# v3_1.net
KiCad netlist of a schematic drawn in EasyEDA Pro
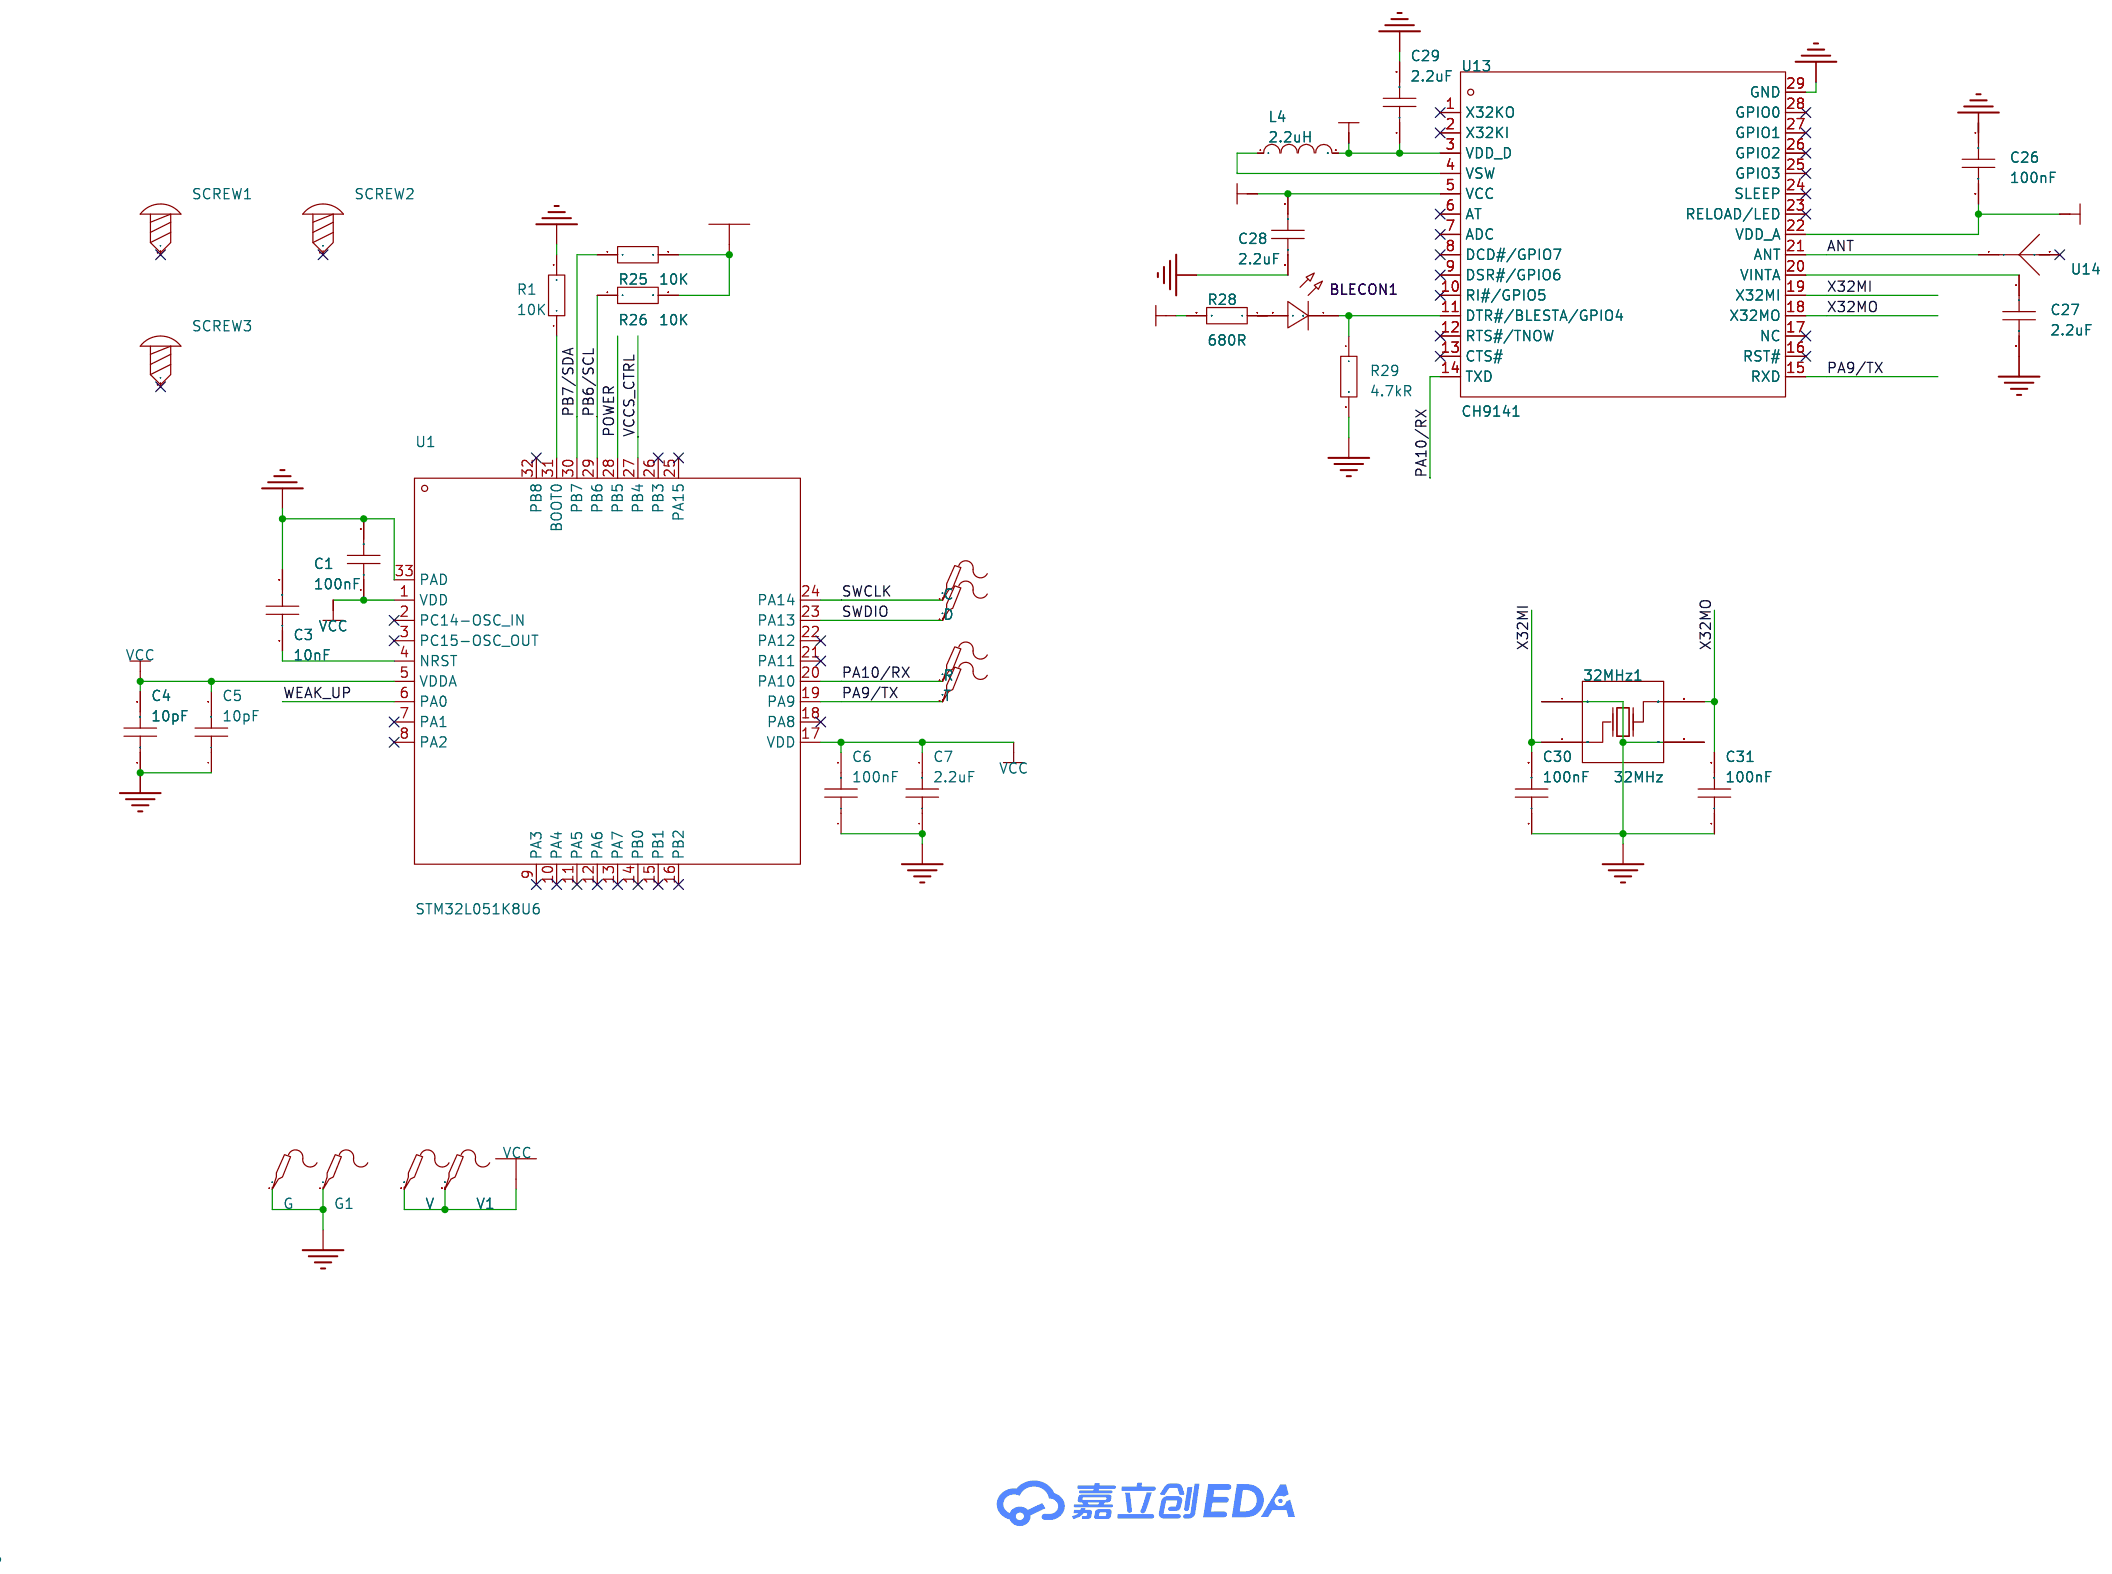
[diagram p0: 主控]
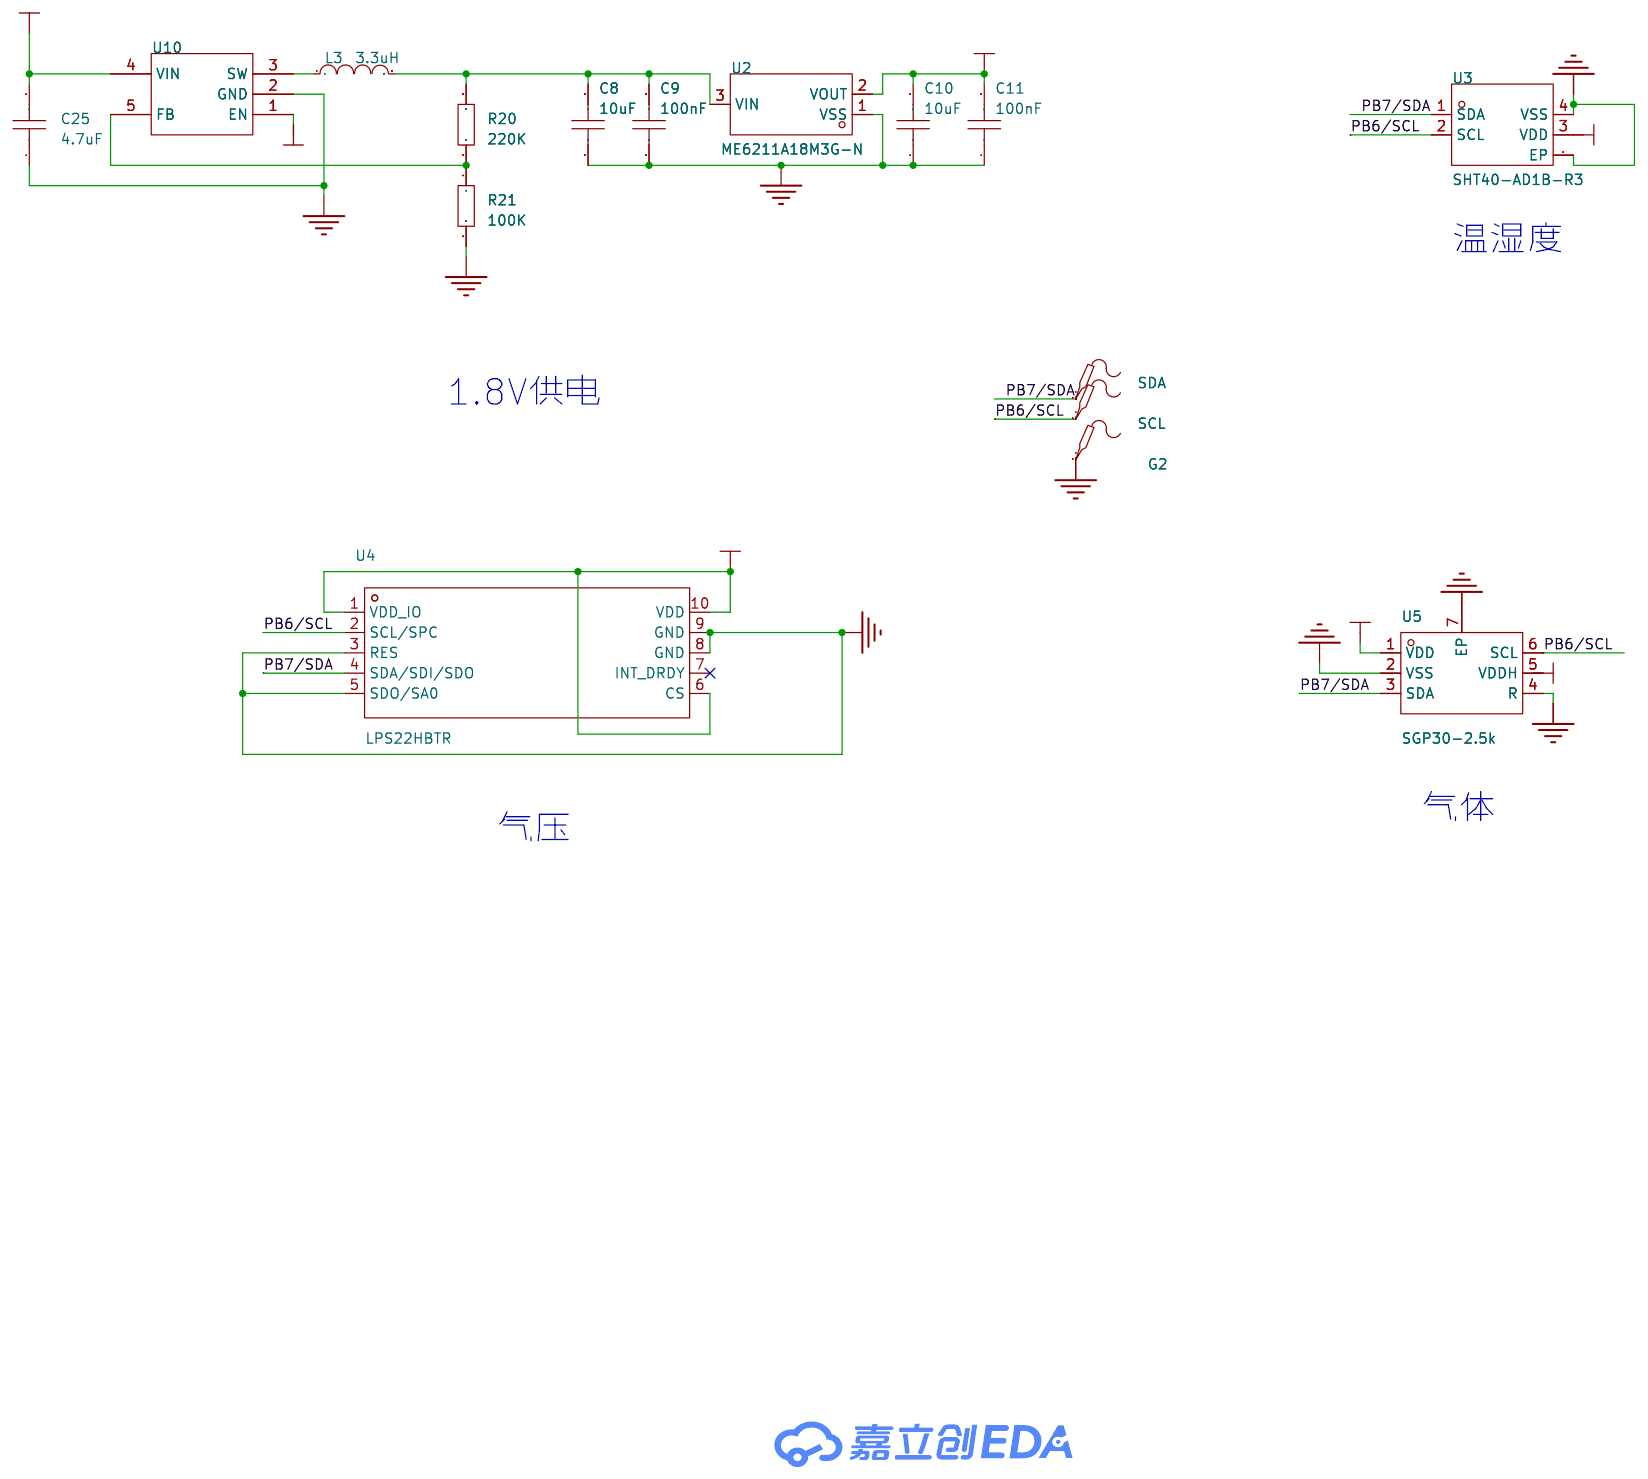
[diagram p1: 传感器]
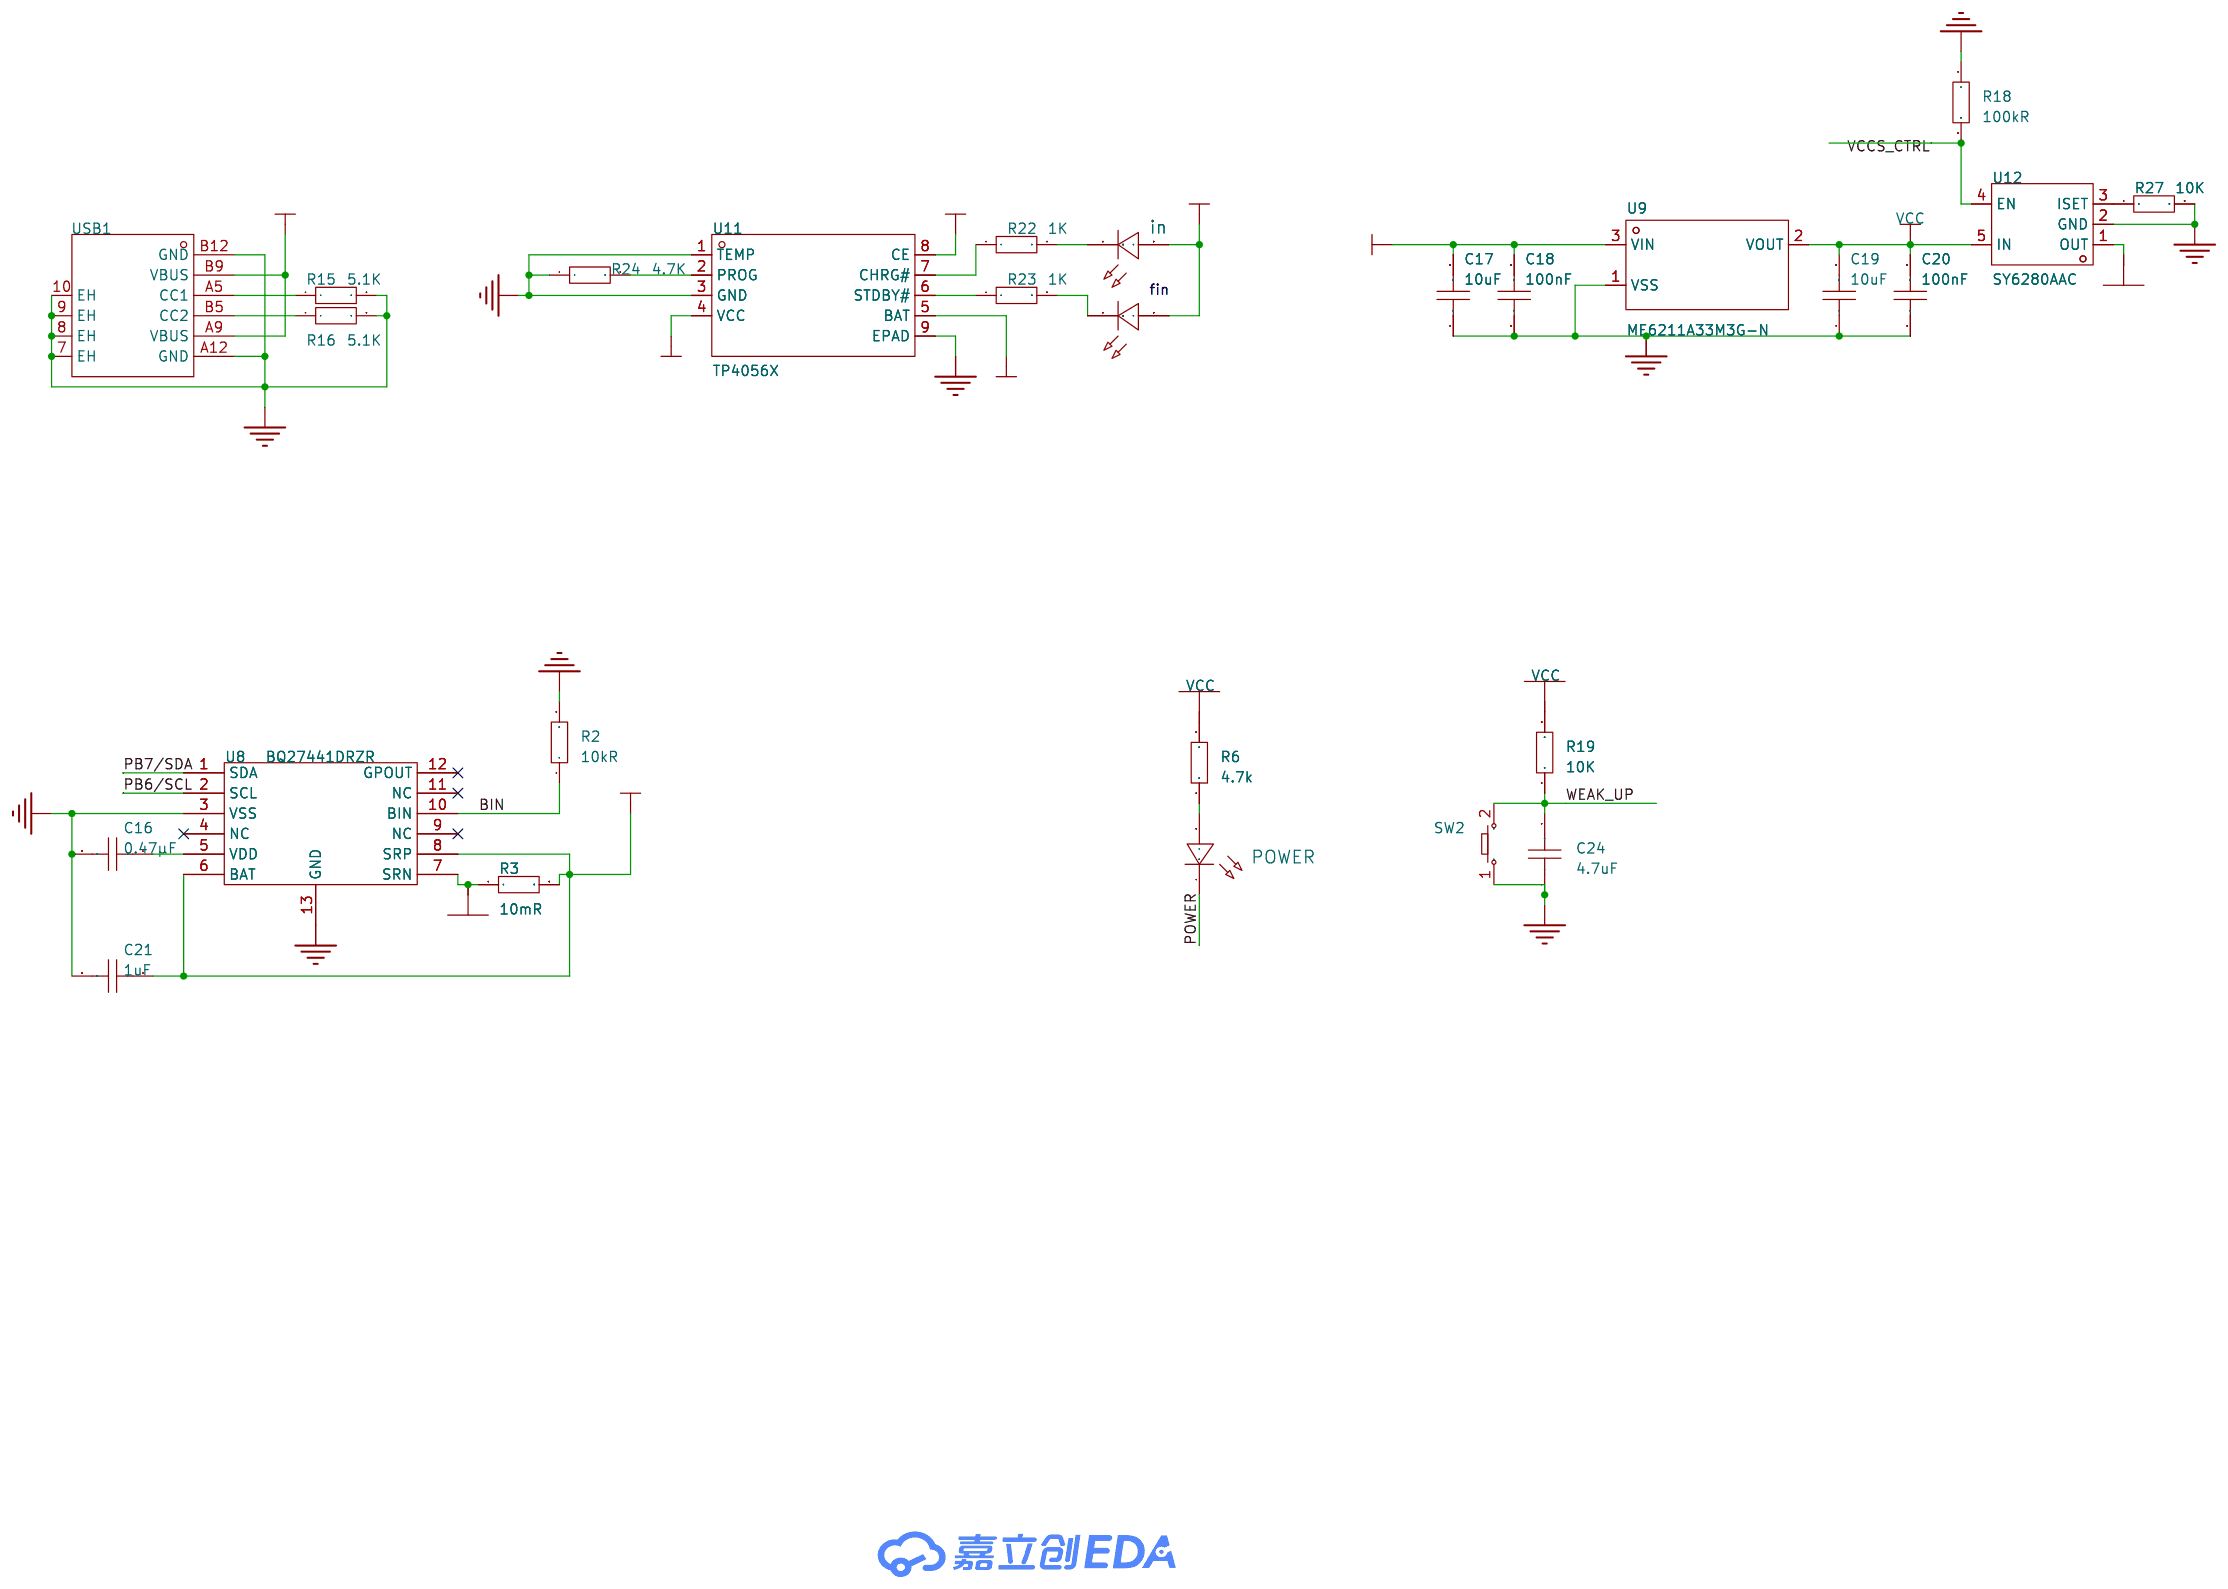
[diagram p2: 电源]

(export (version "E")
  (design (tool "Eeschema 10.0.6"))
  (components
    (comp (ref "32MHz1")
      (value "32MHz")
      (footprint "easyedapro:OSC-SMD_4P-L3.2-W2.5-BL")
      (description "晶振类型:贴片晶振;频率:32MHz;常温频差:±10ppm;外接负载电容:10pF;频率稳定度(全温):±20ppm;")
      (fields (field (name "Manufacturer Part") "X322532MMB4SI") (field (name "Manufacturer") "YXC(扬兴晶振)"))
      (libsource (lib "easyedapro") (part "X322532MMB4SI"))
    )
    (comp (ref "BLECON1")
      (value "~")
      (footprint "easyedapro:LED_0603")
      (libsource (lib "easyedapro") (part "LED_B"))
    )
    (comp (ref "C")
      (value "~")
      (footprint "easyedapro:Test-Point-0.5mm")
      (description "Test Point 测试点")
      (libsource (lib "easyedapro") (part "Test-Point"))
    )
    (comp (ref "C1")
      (value "100nF")
      (footprint "easyedapro:C0603")
      (libsource (lib "easyedapro") (part "CapAcitance"))
    )
    (comp (ref "C3")
      (value "10nF")
      (footprint "easyedapro:C0603")
      (libsource (lib "easyedapro") (part "CapAcitance"))
    )
    (comp (ref "C4")
      (value "10pF")
      (footprint "easyedapro:C0603")
      (libsource (lib "easyedapro") (part "CapAcitance"))
    )
    (comp (ref "C5")
      (value "10pF")
      (footprint "easyedapro:C0603")
      (libsource (lib "easyedapro") (part "CapAcitance"))
    )
    (comp (ref "C6")
      (value "100nF")
      (footprint "easyedapro:C0603")
      (libsource (lib "easyedapro") (part "CapAcitance"))
    )
    (comp (ref "C7")
      (value "2.2uF")
      (footprint "easyedapro:C0603")
      (libsource (lib "easyedapro") (part "CapAcitance"))
    )
    (comp (ref "C26")
      (value "100nF")
      (footprint "easyedapro:C0603")
      (libsource (lib "easyedapro") (part "CapAcitance"))
    )
    (comp (ref "C27")
      (value "2.2uF")
      (footprint "easyedapro:C0603")
      (libsource (lib "easyedapro") (part "CapAcitance"))
    )
    (comp (ref "C28")
      (value "2.2uF")
      (footprint "easyedapro:C0603")
      (libsource (lib "easyedapro") (part "CapAcitance"))
    )
    (comp (ref "C29")
      (value "2.2uF")
      (footprint "easyedapro:C0603")
      (libsource (lib "easyedapro") (part "CapAcitance"))
    )
    (comp (ref "C30")
      (value "100nF")
      (footprint "easyedapro:C0603")
      (libsource (lib "easyedapro") (part "CapAcitance"))
    )
    (comp (ref "C31")
      (value "100nF")
      (footprint "easyedapro:C0603")
      (libsource (lib "easyedapro") (part "CapAcitance"))
    )
    (comp (ref "D")
      (value "~")
      (footprint "easyedapro:Test-Point-0.5mm")
      (description "Test Point 测试点")
      (libsource (lib "easyedapro") (part "Test-Point"))
    )
    (comp (ref "G")
      (value "~")
      (footprint "easyedapro:Test-Point-0.5mm")
      (description "Test Point 测试点")
      (libsource (lib "easyedapro") (part "Test-Point"))
    )
    (comp (ref "G1")
      (value "~")
      (footprint "easyedapro:Test-Point-0.5mm")
      (description "Test Point 测试点")
      (libsource (lib "easyedapro") (part "Test-Point"))
    )
    (comp (ref "L4")
      (value "2.2uH")
      (footprint "easyedapro:L0603")
      (libsource (lib "easyedapro") (part "SDFL1608S100KTF"))
    )
    (comp (ref "R")
      (value "~")
      (footprint "easyedapro:Test-Point-0.5mm")
      (description "Test Point 测试点")
      (libsource (lib "easyedapro") (part "Test-Point"))
    )
    (comp (ref "R1") (value "10K") (footprint "easyedapro:R0603") (libsource (lib "easyedapro") (part "电阻")))
    (comp (ref "R25") (value "10K") (footprint "easyedapro:R0603") (libsource (lib "easyedapro") (part "电阻")))
    (comp (ref "R26") (value "10K") (footprint "easyedapro:R0603") (libsource (lib "easyedapro") (part "电阻")))
    (comp (ref "R28")
      (value "680R")
      (footprint "easyedapro:R0603")
      (libsource (lib "easyedapro") (part "电阻"))
    )
    (comp (ref "R29")
      (value "4.7kR")
      (footprint "easyedapro:R0603")
      (libsource (lib "easyedapro") (part "电阻"))
    )
    (comp (ref "SCREW1")
      (value "~")
      (footprint "easyedapro:M2螺丝")
      (libsource (lib "easyedapro") (part "螺丝孔"))
    )
    (comp (ref "SCREW2")
      (value "~")
      (footprint "easyedapro:M2螺丝")
      (libsource (lib "easyedapro") (part "螺丝孔"))
    )
    (comp (ref "SCREW3")
      (value "~")
      (footprint "easyedapro:M2螺丝")
      (libsource (lib "easyedapro") (part "螺丝孔"))
    )
    (comp (ref "T")
      (value "~")
      (footprint "easyedapro:Test-Point-0.5mm")
      (description "Test Point 测试点")
      (libsource (lib "easyedapro") (part "Test-Point"))
    )
    (comp (ref "U1")
      (value "STM32L051K8U6")
      (footprint "easyedapro:UFQFPN-32_L5.0-W5.0-P0.50-BL-EP")
      (description "CPU内核:ARM-M系列;CPU最大主频:32MHz;应用领域:-;")
      (fields (field (name "Manufacturer") "ST(意法半导体)"))
      (libsource (lib "easyedapro") (part "STM32L051K8U6"))
    )
    (comp (ref "U13")
      (value "CH9141")
      (footprint "easyedapro:qfn-28_l4.0-w4.0-p0.40-bl-ep2.7")
      (fields (field (name "Manufacturer") "WCH(南京沁恒)"))
      (libsource (lib "easyedapro") (part "CH9141"))
    )
    (comp (ref "U14")
      (value "~")
      (footprint "easyedapro:SMD，3.5x1.8")
      (libsource (lib "easyedapro") (part "T3518"))
    )
    (comp (ref "V")
      (value "~")
      (footprint "easyedapro:Test-Point-0.5mm")
      (description "Test-Point")
      (libsource (lib "") (part "Test-Point_1"))
    )
    (comp (ref "V1")
      (value "~")
      (footprint "easyedapro:Test-Point-0.5mm")
      (description "Test-Point")
      (libsource (lib "") (part "Test-Point_1"))
    )
    (comp (ref "C8")
      (value "10uF")
      (footprint "easyedapro:C0603")
      (libsource (lib "easyedapro") (part "CapAcitance"))
    )
    (comp (ref "C9")
      (value "100nF")
      (footprint "easyedapro:C0603")
      (libsource (lib "easyedapro") (part "CapAcitance"))
    )
    (comp (ref "C10")
      (value "10uF")
      (footprint "easyedapro:C0603")
      (libsource (lib "easyedapro") (part "CapAcitance"))
    )
    (comp (ref "C11")
      (value "100nF")
      (footprint "easyedapro:C0603")
      (libsource (lib "easyedapro") (part "CapAcitance"))
    )
    (comp (ref "C25")
      (value "4.7uF")
      (footprint "easyedapro:C0603")
      (libsource (lib "easyedapro") (part "CapAcitance"))
    )
    (comp (ref "G2")
      (value "~")
      (footprint "easyedapro:Test-Point-0.5mm")
      (description "Test-Point")
      (libsource (lib "easyedapro") (part "Test-Point"))
    )
    (comp (ref "L3")
      (value "3.3uH")
      (footprint "easyedapro:IND-SMD_L2.5-W2.0_SWPA2520")
      (description "电感值:2.2uH;精度:±20%;额定电流:1.25A;直流电阻(DCR):216mΩ;")
      (fields
        (field (name "Manufacturer Part") "SWPA252012S2R2MT")
        (field (name "Manufacturer") "Sunlord(顺络)")
      )
      (libsource (lib "easyedapro") (part "SWPA252012S-2R2MT"))
    )
    (comp (ref "R20")
      (value "220K")
      (footprint "easyedapro:R0603")
      (libsource (lib "easyedapro") (part "电阻"))
    )
    (comp (ref "R21")
      (value "100K")
      (footprint "easyedapro:R0603")
      (libsource (lib "easyedapro") (part "电阻"))
    )
    (comp (ref "SCL")
      (value "~")
      (footprint "easyedapro:Test-Point-0.5mm")
      (description "Test-Point")
      (libsource (lib "easyedapro") (part "Test-Point"))
    )
    (comp (ref "SDA")
      (value "~")
      (footprint "easyedapro:Test-Point-0.5mm")
      (description "Test-Point")
      (libsource (lib "easyedapro") (part "Test-Point"))
    )
    (comp (ref "U2")
      (value "ME6211A18M3G-N")
      (footprint "easyedapro:SOT-23-3_L3.0-W1.7-P0.95-LS2.9-BR")
      (description "输出类型:固定;最大输入电压:6V;输出电压:1.8V;最大输出电流:300mA;电源纹波抑制比(PSRR):70dB;输出极性:正极;")
      (fields (field (name "Manufacturer") "MICRONE(南京微盟)"))
      (libsource (lib "easyedapro") (part "ME6211A18M3G-N"))
    )
    (comp (ref "U3")
      (value "SHT40-AD1B-R3")
      (footprint "easyedapro:DFN-4_L1.5-W1.5-P0.8-TL-EP")
      (description "3.000.353")
      (fields (field (name "Manufacturer") "Sensirion(瑞士盛思锐)"))
      (libsource (lib "easyedapro") (part "SHT40-AD1B-R3"))
    )
    (comp (ref "U4")
      (value "LPS22HBTR")
      (footprint "easyedapro:HLGA-10L_LPS22HBTR")
      (fields (field (name "Manufacturer") "ST(意法半导体)"))
      (libsource (lib "easyedapro") (part "LPS22HBTR"))
    )
    (comp (ref "U5")
      (value "SGP30-2.5k")
      (footprint "easyedapro:DFN-6_L2.5-W2.5-P0.8-BL-EP")
      (description "气体类型:空气质量;精度:±10%;")
      (fields (field (name "Manufacturer") "Sensirion(瑞士盛思锐)"))
      (libsource (lib "easyedapro") (part "SGP30-2.5K"))
    )
    (comp (ref "U10")
      (value "~")
      (footprint "easyedapro:SOT-23-5_L2.9-W1.6-P0.95-LS2.8-TL")
      (libsource (lib "easyedapro") (part "TLV62569DBVR"))
    )
    (comp (ref "C16")
      (value "0.47μF")
      (footprint "easyedapro:C0603")
      (libsource (lib "easyedapro") (part "CapAcitance"))
    )
    (comp (ref "C17")
      (value "10uF")
      (footprint "easyedapro:C0603")
      (libsource (lib "easyedapro") (part "CapAcitance"))
    )
    (comp (ref "C18")
      (value "100nF")
      (footprint "easyedapro:C0603")
      (libsource (lib "easyedapro") (part "CapAcitance"))
    )
    (comp (ref "C19")
      (value "10uF")
      (footprint "easyedapro:C0603")
      (libsource (lib "easyedapro") (part "CapAcitance"))
    )
    (comp (ref "C20")
      (value "100nF")
      (footprint "easyedapro:C0603")
      (libsource (lib "easyedapro") (part "CapAcitance"))
    )
    (comp (ref "C21")
      (value "1uF")
      (footprint "easyedapro:C0603")
      (libsource (lib "easyedapro") (part "CapAcitance"))
    )
    (comp (ref "C24")
      (value "4.7uF")
      (footprint "easyedapro:C0603")
      (libsource (lib "easyedapro") (part "CapAcitance"))
    )
    (comp (ref "fin")
      (value "~")
      (footprint "easyedapro:LED_0603")
      (libsource (lib "easyedapro") (part "LED_G"))
    )
    (comp (ref "in")
      (value "~")
      (footprint "easyedapro:LED_0603")
      (libsource (lib "easyedapro") (part "LED_R"))
    )
    (comp (ref "POWER")
      (value "~")
      (footprint "easyedapro:LED_0603")
      (libsource (lib "easyedapro") (part "LED_R"))
    )
    (comp (ref "R2") (value "10kR") (libsource (lib "easyedapro") (part "电阻")))
    (comp (ref "R3") (value "10mR") (libsource (lib "easyedapro") (part "电阻")))
    (comp (ref "R6") (value "4.7k") (footprint "easyedapro:R0603") (libsource (lib "easyedapro") (part "电阻")))
    (comp (ref "R15")
      (value "5.1K")
      (footprint "easyedapro:R0603")
      (libsource (lib "easyedapro") (part "电阻"))
    )
    (comp (ref "R16")
      (value "5.1K")
      (footprint "easyedapro:R0603")
      (libsource (lib "easyedapro") (part "电阻"))
    )
    (comp (ref "R18") (value "100kR") (libsource (lib "easyedapro") (part "电阻")))
    (comp (ref "R19") (value "10K") (footprint "easyedapro:R0603") (libsource (lib "easyedapro") (part "电阻")))
    (comp (ref "R22") (value "1K") (footprint "easyedapro:R0603") (libsource (lib "easyedapro") (part "电阻")))
    (comp (ref "R23") (value "1K") (footprint "easyedapro:R0603") (libsource (lib "easyedapro") (part "电阻")))
    (comp (ref "R24")
      (value "4.7K")
      (footprint "easyedapro:R0603")
      (libsource (lib "easyedapro") (part "电阻"))
    )
    (comp (ref "R27") (value "10K") (footprint "easyedapro:R0603") (libsource (lib "easyedapro") (part "电阻")))
    (comp (ref "SW2")
      (value "~")
      (footprint "easyedapro:Key_SMD_3.6x6.1x2.5")
      (libsource (lib "easyedapro") (part "轻触按键x2"))
    )
    (comp (ref "U8")
      (value "BQ27441DRZR")
      (footprint "easyedapro:VSON-12")
      (libsource (lib "easyedapro") (part "BQ27441DRZR"))
    )
    (comp (ref "U9")
      (value "ME6211A33M3G-N")
      (footprint "easyedapro:SOT-23-3_L2.9-W1.6-P1.90-LS2.8-BR")
      (description "输出类型:固定;最大输入电压:6V;输出电压:3.3V;最大输出电流:500mA;电源纹波抑制比(PSRR):70dB;输出极性:正极;")
      (fields (field (name "Manufacturer") "MICRONE(南京微盟)"))
      (libsource (lib "easyedapro") (part "ME6211A33M3G-N"))
    )
    (comp (ref "U11")
      (value "TP4056X")
      (footprint "easyedapro:SOP-8_L4.9-W3.9-P1.27-LS6.0-BL-EP")
      (description "充电电池的类型:-;电池单元组数:-;最大充电电流:-;充满的电池组电压:-;最大供应电压:-;")
      (fields (field (name "Manufacturer") "TOPPOWER(南京拓微)"))
      (libsource (lib "easyedapro") (part "TP4056X"))
    )
    (comp (ref "U12")
      (value "SY6280AAC")
      (footprint "easyedapro:SOT-23-5_L3.0-W1.7-P0.95-LS2.8-BR")
      (description "低能耗配电开关")
      (fields (field (name "Manufacturer") "矽力杰silergy"))
      (libsource (lib "easyedapro") (part "SY6280AAC"))
    )
    (comp (ref "USB1")
      (value "~")
      (footprint "easyedapro:USB_ TYPE-C-6P")
      (libsource (lib "easyedapro") (part "USB_ TYPE-C-6P"))
    )
  )
  (nets
    (net (code "1") (name "1.8V") (class "Default")
      (node (ref "C10") (pin "2") (pinfunction "2_2") (pintype "input"))
      (node (ref "C11") (pin "2") (pinfunction "2_2") (pintype "input"))
      (node (ref "U2") (pin "2") (pinfunction "VOUT_2") (pintype "unspecified"))
      (node (ref "U5") (pin "1") (pinfunction "VDD_1") (pintype "unspecified"))
      (node (ref "U5") (pin "5") (pinfunction "VDDH_5") (pintype "unspecified"))
    )
    (net (code "2") (name "ANT") (class "Default")
      (node (ref "U13") (pin "21") (pinfunction "ANT_21") (pintype "unspecified"))
      (node (ref "U14") (pin "1") (pinfunction "1_1") (pintype "unspecified"))
    )
    (net (code "3") (name "BAT") (class "Default")
      (node (ref "R3") (pin "1") (pinfunction "1_1") (pintype "input"))
      (node (ref "U8") (pin "7") (pinfunction "SRN_7") (pintype "input"))
    )
    (net (code "4") (name "BIN") (class "Default")
      (node (ref "R2") (pin "1") (pinfunction "1_1") (pintype "input"))
      (node (ref "U8") (pin "10") (pinfunction "BIN_10") (pintype "input"))
    )
    (net (code "5") (name "GND") (class "Default")
      (node (ref "32MHz1") (pin "2") (pinfunction "GND_2") (pintype "input"))
      (node (ref "32MHz1") (pin "4") (pinfunction "GND_4") (pintype "input"))
      (node (ref "C1") (pin "2") (pinfunction "2_2") (pintype "input"))
      (node (ref "C10") (pin "1") (pinfunction "1_1") (pintype "input"))
      (node (ref "C11") (pin "1") (pinfunction "1_1") (pintype "input"))
      (node (ref "C16") (pin "2") (pinfunction "2_2") (pintype "input"))
      (node (ref "C17") (pin "1") (pinfunction "1_1") (pintype "input"))
      (node (ref "C18") (pin "1") (pinfunction "1_1") (pintype "input"))
      (node (ref "C19") (pin "1") (pinfunction "1_1") (pintype "input"))
      (node (ref "C20") (pin "1") (pinfunction "1_1") (pintype "input"))
      (node (ref "C21") (pin "2") (pinfunction "2_2") (pintype "input"))
      (node (ref "C24") (pin "1") (pinfunction "1_1") (pintype "input"))
      (node (ref "C25") (pin "1") (pinfunction "1_1") (pintype "input"))
      (node (ref "C26") (pin "1") (pinfunction "1_1") (pintype "input"))
      (node (ref "C27") (pin "2") (pinfunction "2_2") (pintype "input"))
      (node (ref "C28") (pin "2") (pinfunction "2_2") (pintype "input"))
      (node (ref "C29") (pin "2") (pinfunction "2_2") (pintype "input"))
      (node (ref "C3") (pin "2") (pinfunction "2_2") (pintype "input"))
      (node (ref "C30") (pin "1") (pinfunction "1_1") (pintype "input"))
      (node (ref "C31") (pin "1") (pinfunction "1_1") (pintype "input"))
      (node (ref "C4") (pin "1") (pinfunction "1_1") (pintype "input"))
      (node (ref "C5") (pin "1") (pinfunction "1_1") (pintype "input"))
      (node (ref "C6") (pin "1") (pinfunction "1_1") (pintype "input"))
      (node (ref "C7") (pin "1") (pinfunction "1_1") (pintype "input"))
      (node (ref "C8") (pin "1") (pinfunction "1_1") (pintype "input"))
      (node (ref "C9") (pin "1") (pinfunction "1_1") (pintype "input"))
      (node (ref "G") (pin "1") (pinfunction "1_1") (pintype "input"))
      (node (ref "G1") (pin "1") (pinfunction "1_1") (pintype "input"))
      (node (ref "G2") (pin "1") (pinfunction "1_1") (pintype "input"))
      (node (ref "R1") (pin "2") (pinfunction "2_2") (pintype "input"))
      (node (ref "R15") (pin "2") (pinfunction "2_2") (pintype "input"))
      (node (ref "R16") (pin "2") (pinfunction "2_2") (pintype "input"))
      (node (ref "R18") (pin "1") (pinfunction "1_1") (pintype "input"))
      (node (ref "R2") (pin "2") (pinfunction "2_2") (pintype "input"))
      (node (ref "R21") (pin "2") (pinfunction "2_2") (pintype "input"))
      (node (ref "R24") (pin "1") (pinfunction "1_1") (pintype "input"))
      (node (ref "R27") (pin "2") (pinfunction "2_2") (pintype "input"))
      (node (ref "R29") (pin "2") (pinfunction "2_2") (pintype "input"))
      (node (ref "SW2") (pin "1") (pinfunction "1_1") (pintype "input"))
      (node (ref "U1") (pin "33") (pinfunction "PAD_33") (pintype "unspecified"))
      (node (ref "U10") (pin "2") (pinfunction "GND_2") (pintype "input"))
      (node (ref "U11") (pin "1") (pinfunction "TEMP_1") (pintype "input"))
      (node (ref "U11") (pin "3") (pinfunction "GND_3") (pintype "input"))
      (node (ref "U11") (pin "9") (pinfunction "EPAD_9") (pintype "input"))
      (node (ref "U12") (pin "2") (pinfunction "GND_2") (pintype "input"))
      (node (ref "U13") (pin "29") (pinfunction "GND_29") (pintype "unspecified"))
      (node (ref "U2") (pin "1") (pinfunction "VSS_1") (pintype "unspecified"))
      (node (ref "U3") (pin "4") (pinfunction "VSS_4") (pintype "unspecified"))
      (node (ref "U3") (pin "5") (pinfunction "EP_5") (pintype "unspecified"))
      (node (ref "U4") (pin "3") (pinfunction "RES_3") (pintype "unspecified"))
      (node (ref "U4") (pin "5") (pinfunction "SDO/SA0_5") (pintype "unspecified"))
      (node (ref "U4") (pin "8") (pinfunction "GND_8") (pintype "unspecified"))
      (node (ref "U4") (pin "9") (pinfunction "GND_9") (pintype "unspecified"))
      (node (ref "U5") (pin "2") (pinfunction "VSS_2") (pintype "unspecified"))
      (node (ref "U5") (pin "4") (pinfunction "R_4") (pintype "unspecified"))
      (node (ref "U5") (pin "7") (pinfunction "EP_7") (pintype "unspecified"))
      (node (ref "U8") (pin "13") (pinfunction "GND_13") (pintype "input"))
      (node (ref "U8") (pin "3") (pinfunction "VSS_3") (pintype "input"))
      (node (ref "U9") (pin "1") (pinfunction "VSS_1") (pintype "unspecified"))
      (node (ref "USB1") (pin "10") (pinfunction "EH_10") (pintype "input"))
      (node (ref "USB1") (pin "7") (pinfunction "EH_7") (pintype "input"))
      (node (ref "USB1") (pin "8") (pinfunction "EH_8") (pintype "input"))
      (node (ref "USB1") (pin "9") (pinfunction "EH_9") (pintype "input"))
      (node (ref "USB1") (pin "A12") (pinfunction "GND_A12") (pintype "input"))
      (node (ref "USB1") (pin "B12") (pinfunction "GND_B12") (pintype "input"))
    )
    (net (code "6") (name "Net-(BLECON1-A)") (class "Default")
      (node (ref "BLECON1") (pin "2") (pinfunction "A_2") (pintype "input"))
      (node (ref "R28") (pin "1") (pinfunction "1_1") (pintype "input"))
    )
    (net (code "7") (name "Net-(BLECON1-C)") (class "Default")
      (node (ref "BLECON1") (pin "1") (pinfunction "C_1") (pintype "input"))
      (node (ref "R29") (pin "1") (pinfunction "1_1") (pintype "input"))
      (node (ref "U13") (pin "11") (pinfunction "DTR#/BLESTA/GPIO4_11") (pintype "unspecified"))
    )
    (net (code "8") (name "Net-(POWER-A)") (class "Default")
      (node (ref "POWER") (pin "2") (pinfunction "A_2") (pintype "input"))
      (node (ref "R6") (pin "1") (pinfunction "1_1") (pintype "input"))
    )
    (net (code "9") (name "Net-(U1-BOOT0)") (class "Default")
      (node (ref "R1") (pin "1") (pinfunction "1_1") (pintype "input"))
      (node (ref "U1") (pin "31") (pinfunction "BOOT0_31") (pintype "unspecified"))
    )
    (net (code "10") (name "Net-(U1-NRST)") (class "Default")
      (node (ref "C3") (pin "1") (pinfunction "1_1") (pintype "input"))
      (node (ref "U1") (pin "4") (pinfunction "NRST_4") (pintype "unspecified"))
    )
    (net (code "11") (name "Net-(U2-VIN)") (class "Default")
      (node (ref "C8") (pin "2") (pinfunction "2_2") (pintype "input"))
      (node (ref "C9") (pin "2") (pinfunction "2_2") (pintype "input"))
      (node (ref "L3") (pin "2") (pinfunction "2_2") (pintype "input"))
      (node (ref "R20") (pin "2") (pinfunction "2_2") (pintype "input"))
      (node (ref "U2") (pin "3") (pinfunction "VIN_3") (pintype "unspecified"))
    )
    (net (code "12") (name "Net-(U8-VDD)") (class "Default")
      (node (ref "C16") (pin "1") (pinfunction "1_1") (pintype "input"))
      (node (ref "U8") (pin "5") (pinfunction "VDD_5") (pintype "input"))
    )
    (net (code "13") (name "Net-(U10-FB)") (class "Default")
      (node (ref "R20") (pin "1") (pinfunction "1_1") (pintype "input"))
      (node (ref "R21") (pin "1") (pinfunction "1_1") (pintype "input"))
      (node (ref "U10") (pin "5") (pinfunction "FB_5") (pintype "input"))
    )
    (net (code "14") (name "Net-(U10-SW)") (class "Default")
      (node (ref "L3") (pin "1") (pinfunction "1_1") (pintype "input"))
      (node (ref "U10") (pin "3") (pinfunction "SW_3") (pintype "input"))
    )
    (net (code "15") (name "Net-(U11-CHRG#)") (class "Default")
      (node (ref "R22") (pin "1") (pinfunction "1_1") (pintype "input"))
      (node (ref "U11") (pin "7") (pinfunction "CHRG#_7") (pintype "input"))
    )
    (net (code "16") (name "Net-(U11-PROG)") (class "Default")
      (node (ref "R24") (pin "2") (pinfunction "2_2") (pintype "input"))
      (node (ref "U11") (pin "2") (pinfunction "PROG_2") (pintype "input"))
    )
    (net (code "17") (name "Net-(U11-STDBY#)") (class "Default")
      (node (ref "R23") (pin "1") (pinfunction "1_1") (pintype "input"))
      (node (ref "U11") (pin "6") (pinfunction "STDBY#_6") (pintype "input"))
    )
    (net (code "18") (name "Net-(U12-ISET)") (class "Default")
      (node (ref "R27") (pin "1") (pinfunction "1_1") (pintype "input"))
      (node (ref "U12") (pin "3") (pinfunction "ISET_3") (pintype "input"))
    )
    (net (code "19") (name "Net-(U13-VINTA)") (class "Default")
      (node (ref "C27") (pin "1") (pinfunction "1_1") (pintype "input"))
      (node (ref "U13") (pin "20") (pinfunction "VINTA_20") (pintype "unspecified"))
    )
    (net (code "20") (name "Net-(U13-VSW)") (class "Default")
      (node (ref "L4") (pin "1") (pinfunction "1_1") (pintype "unspecified"))
      (node (ref "U13") (pin "4") (pinfunction "VSW_4") (pintype "unspecified"))
    )
    (net (code "21") (name "Net-(USB1-CC1)") (class "Default")
      (node (ref "R15") (pin "1") (pinfunction "1_1") (pintype "input"))
      (node (ref "USB1") (pin "A5") (pinfunction "CC1_A5") (pintype "input"))
    )
    (net (code "22") (name "Net-(USB1-CC2)") (class "Default")
      (node (ref "R16") (pin "1") (pinfunction "1_1") (pintype "input"))
      (node (ref "USB1") (pin "B5") (pinfunction "CC2_B5") (pintype "input"))
    )
    (net (code "23") (name "Net-(fin-C)") (class "Default")
      (node (ref "R23") (pin "2") (pinfunction "2_2") (pintype "input"))
      (node (ref "fin") (pin "1") (pinfunction "C_1") (pintype "input"))
    )
    (net (code "24") (name "Net-(in-C)") (class "Default")
      (node (ref "R22") (pin "2") (pinfunction "2_2") (pintype "input"))
      (node (ref "in") (pin "1") (pinfunction "C_1") (pintype "input"))
    )
    (net (code "25") (name "PA9{slash}TX") (class "Default")
      (node (ref "T") (pin "1") (pinfunction "1_1") (pintype "input"))
      (node (ref "U1") (pin "19") (pinfunction "PA9_19") (pintype "unspecified"))
      (node (ref "U13") (pin "15") (pinfunction "RXD_15") (pintype "unspecified"))
    )
    (net (code "26") (name "PA10{slash}RX") (class "Default")
      (node (ref "R") (pin "1") (pinfunction "1_1") (pintype "input"))
      (node (ref "U1") (pin "20") (pinfunction "PA10_20") (pintype "unspecified"))
      (node (ref "U13") (pin "14") (pinfunction "TXD_14") (pintype "unspecified"))
    )
    (net (code "27") (name "PB6{slash}SCL") (class "Default")
      (node (ref "R26") (pin "1") (pinfunction "1_1") (pintype "input"))
      (node (ref "SCL") (pin "1") (pinfunction "1_1") (pintype "input"))
      (node (ref "U1") (pin "29") (pinfunction "PB6_29") (pintype "unspecified"))
      (node (ref "U3") (pin "2") (pinfunction "SCL_2") (pintype "unspecified"))
      (node (ref "U4") (pin "2") (pinfunction "SCL/SPC_2") (pintype "unspecified"))
      (node (ref "U5") (pin "6") (pinfunction "SCL_6") (pintype "unspecified"))
      (node (ref "U8") (pin "2") (pinfunction "SCL_2") (pintype "input"))
    )
    (net (code "28") (name "PB7{slash}SDA") (class "Default")
      (node (ref "R25") (pin "1") (pinfunction "1_1") (pintype "input"))
      (node (ref "SDA") (pin "1") (pinfunction "1_1") (pintype "input"))
      (node (ref "U1") (pin "30") (pinfunction "PB7_30") (pintype "unspecified"))
      (node (ref "U3") (pin "1") (pinfunction "SDA_1") (pintype "unspecified"))
      (node (ref "U4") (pin "4") (pinfunction "SDA/SDI/SDO_4") (pintype "unspecified"))
      (node (ref "U5") (pin "3") (pinfunction "SDA_3") (pintype "unspecified"))
      (node (ref "U8") (pin "1") (pinfunction "SDA_1") (pintype "input"))
    )
    (net (code "29") (name "POWER") (class "Default")
      (node (ref "POWER") (pin "1") (pinfunction "C_1") (pintype "input"))
      (node (ref "U1") (pin "28") (pinfunction "PB5_28") (pintype "unspecified"))
    )
    (net (code "30") (name "SWCLK") (class "Default")
      (node (ref "C") (pin "1") (pinfunction "1_1") (pintype "input"))
      (node (ref "U1") (pin "24") (pinfunction "PA14_24") (pintype "unspecified"))
    )
    (net (code "31") (name "SWDIO") (class "Default")
      (node (ref "D") (pin "1") (pinfunction "1_1") (pintype "input"))
      (node (ref "U1") (pin "23") (pinfunction "PA13_23") (pintype "unspecified"))
    )
    (net (code "32") (name "VBAT") (class "Default")
      (node (ref "C17") (pin "2") (pinfunction "2_2") (pintype "input"))
      (node (ref "C18") (pin "2") (pinfunction "2_2") (pintype "input"))
      (node (ref "C21") (pin "1") (pinfunction "1_1") (pintype "input"))
      (node (ref "R3") (pin "2") (pinfunction "2_2") (pintype "input"))
      (node (ref "U11") (pin "5") (pinfunction "BAT_5") (pintype "input"))
      (node (ref "U8") (pin "6") (pinfunction "BAT_6") (pintype "input"))
      (node (ref "U8") (pin "8") (pinfunction "SRP_8") (pintype "input"))
      (node (ref "U9") (pin "3") (pinfunction "VIN_3") (pintype "unspecified"))
    )
    (net (code "33") (name "VCC") (class "Default")
      (node (ref "C1") (pin "1") (pinfunction "1_1") (pintype "input"))
      (node (ref "C19") (pin "2") (pinfunction "2_2") (pintype "input"))
      (node (ref "C20") (pin "2") (pinfunction "2_2") (pintype "input"))
      (node (ref "C4") (pin "2") (pinfunction "2_2") (pintype "input"))
      (node (ref "C5") (pin "2") (pinfunction "2_2") (pintype "input"))
      (node (ref "C6") (pin "2") (pinfunction "2_2") (pintype "input"))
      (node (ref "C7") (pin "2") (pinfunction "2_2") (pintype "input"))
      (node (ref "R19") (pin "2") (pinfunction "2_2") (pintype "input"))
      (node (ref "R6") (pin "2") (pinfunction "2_2") (pintype "input"))
      (node (ref "U1") (pin "1") (pinfunction "VDD_1") (pintype "unspecified"))
      (node (ref "U1") (pin "17") (pinfunction "VDD_17") (pintype "unspecified"))
      (node (ref "U1") (pin "5") (pinfunction "VDDA_5") (pintype "unspecified"))
      (node (ref "U12") (pin "5") (pinfunction "IN_5") (pintype "input"))
      (node (ref "U9") (pin "2") (pinfunction "VOUT_2") (pintype "unspecified"))
      (node (ref "V") (pin "1") (pinfunction "1_1") (pintype "input"))
      (node (ref "V1") (pin "1") (pinfunction "1_1") (pintype "input"))
    )
    (net (code "34") (name "VCCS") (class "Default")
      (node (ref "C25") (pin "2") (pinfunction "2_2") (pintype "input"))
      (node (ref "C26") (pin "2") (pinfunction "2_2") (pintype "input"))
      (node (ref "C28") (pin "1") (pinfunction "1_1") (pintype "input"))
      (node (ref "C29") (pin "1") (pinfunction "1_1") (pintype "input"))
      (node (ref "L4") (pin "2") (pinfunction "2_2") (pintype "unspecified"))
      (node (ref "R25") (pin "2") (pinfunction "2_2") (pintype "input"))
      (node (ref "R26") (pin "2") (pinfunction "2_2") (pintype "input"))
      (node (ref "R28") (pin "2") (pinfunction "2_2") (pintype "input"))
      (node (ref "U10") (pin "1") (pinfunction "EN_1") (pintype "input"))
      (node (ref "U10") (pin "4") (pinfunction "VIN_4") (pintype "input"))
      (node (ref "U12") (pin "1") (pinfunction "OUT_1") (pintype "input"))
      (node (ref "U13") (pin "22") (pinfunction "VDD_A_22") (pintype "unspecified"))
      (node (ref "U13") (pin "3") (pinfunction "VDD_D_3") (pintype "unspecified"))
      (node (ref "U13") (pin "5") (pinfunction "VCC_5") (pintype "unspecified"))
      (node (ref "U3") (pin "3") (pinfunction "VDD_3") (pintype "unspecified"))
      (node (ref "U4") (pin "1") (pinfunction "VDD_IO_1") (pintype "unspecified"))
      (node (ref "U4") (pin "10") (pinfunction "VDD_10") (pintype "unspecified"))
      (node (ref "U4") (pin "6") (pinfunction "CS_6") (pintype "unspecified"))
    )
    (net (code "35") (name "VCCS_CTRL") (class "Default")
      (node (ref "R18") (pin "2") (pinfunction "2_2") (pintype "input"))
      (node (ref "U1") (pin "27") (pinfunction "PB4_27") (pintype "unspecified"))
      (node (ref "U12") (pin "4") (pinfunction "EN_4") (pintype "input"))
    )
    (net (code "36") (name "VIN") (class "Default")
      (node (ref "U11") (pin "4") (pinfunction "VCC_4") (pintype "input"))
      (node (ref "U11") (pin "8") (pinfunction "CE_8") (pintype "input"))
      (node (ref "USB1") (pin "A9") (pinfunction "VBUS_A9") (pintype "input"))
      (node (ref "USB1") (pin "B9") (pinfunction "VBUS_B9") (pintype "input"))
      (node (ref "fin") (pin "2") (pinfunction "A_2") (pintype "input"))
      (node (ref "in") (pin "2") (pinfunction "A_2") (pintype "input"))
    )
    (net (code "37") (name "WEAK_UP") (class "Default")
      (node (ref "C24") (pin "2") (pinfunction "2_2") (pintype "input"))
      (node (ref "R19") (pin "1") (pinfunction "1_1") (pintype "input"))
      (node (ref "SW2") (pin "2") (pinfunction "2_2") (pintype "input"))
      (node (ref "U1") (pin "6") (pinfunction "PA0_6") (pintype "unspecified"))
    )
    (net (code "38") (name "X32MI") (class "Default")
      (node (ref "32MHz1") (pin "1") (pinfunction "OSC1_1") (pintype "input"))
      (node (ref "C30") (pin "2") (pinfunction "2_2") (pintype "input"))
      (node (ref "U13") (pin "19") (pinfunction "X32MI_19") (pintype "unspecified"))
    )
    (net (code "39") (name "X32MO") (class "Default")
      (node (ref "32MHz1") (pin "3") (pinfunction "OSC2_3") (pintype "input"))
      (node (ref "C31") (pin "2") (pinfunction "2_2") (pintype "input"))
      (node (ref "U13") (pin "18") (pinfunction "X32MO_18") (pintype "unspecified"))
    )
    (net (code "40") (name "unconnected-(SCREW1-Pad1)") (class "Default")
      (node (ref "SCREW1") (pin "1") (pinfunction "1_1") (pintype "input+no_connect"))
    )
    (net (code "41") (name "unconnected-(SCREW2-Pad1)") (class "Default")
      (node (ref "SCREW2") (pin "1") (pinfunction "1_1") (pintype "input+no_connect"))
    )
    (net (code "42") (name "unconnected-(SCREW3-Pad1)") (class "Default")
      (node (ref "SCREW3") (pin "1") (pinfunction "1_1") (pintype "input+no_connect"))
    )
    (net (code "43") (name "unconnected-(U1-PA1-Pad7)") (class "Default")
      (node (ref "U1") (pin "7") (pinfunction "PA1_7") (pintype "unspecified+no_connect"))
    )
    (net (code "44") (name "unconnected-(U1-PA2-Pad8)") (class "Default")
      (node (ref "U1") (pin "8") (pinfunction "PA2_8") (pintype "unspecified+no_connect"))
    )
    (net (code "45") (name "unconnected-(U1-PA3-Pad9)") (class "Default")
      (node (ref "U1") (pin "9") (pinfunction "PA3_9") (pintype "unspecified+no_connect"))
    )
    (net (code "46") (name "unconnected-(U1-PA4-Pad10)") (class "Default")
      (node (ref "U1") (pin "10") (pinfunction "PA4_10") (pintype "unspecified+no_connect"))
    )
    (net (code "47") (name "unconnected-(U1-PA5-Pad11)") (class "Default")
      (node (ref "U1") (pin "11") (pinfunction "PA5_11") (pintype "unspecified+no_connect"))
    )
    (net (code "48") (name "unconnected-(U1-PA6-Pad12)") (class "Default")
      (node (ref "U1") (pin "12") (pinfunction "PA6_12") (pintype "unspecified+no_connect"))
    )
    (net (code "49") (name "unconnected-(U1-PA7-Pad13)") (class "Default")
      (node (ref "U1") (pin "13") (pinfunction "PA7_13") (pintype "unspecified+no_connect"))
    )
    (net (code "50") (name "unconnected-(U1-PA8-Pad18)") (class "Default")
      (node (ref "U1") (pin "18") (pinfunction "PA8_18") (pintype "unspecified+no_connect"))
    )
    (net (code "51") (name "unconnected-(U1-PA11-Pad21)") (class "Default")
      (node (ref "U1") (pin "21") (pinfunction "PA11_21") (pintype "unspecified+no_connect"))
    )
    (net (code "52") (name "unconnected-(U1-PA12-Pad22)") (class "Default")
      (node (ref "U1") (pin "22") (pinfunction "PA12_22") (pintype "unspecified+no_connect"))
    )
    (net (code "53") (name "unconnected-(U1-PA15-Pad25)") (class "Default")
      (node (ref "U1") (pin "25") (pinfunction "PA15_25") (pintype "unspecified+no_connect"))
    )
    (net (code "54") (name "unconnected-(U1-PB0-Pad14)") (class "Default")
      (node (ref "U1") (pin "14") (pinfunction "PB0_14") (pintype "unspecified+no_connect"))
    )
    (net (code "55") (name "unconnected-(U1-PB1-Pad15)") (class "Default")
      (node (ref "U1") (pin "15") (pinfunction "PB1_15") (pintype "unspecified+no_connect"))
    )
    (net (code "56") (name "unconnected-(U1-PB2-Pad16)") (class "Default")
      (node (ref "U1") (pin "16") (pinfunction "PB2_16") (pintype "unspecified+no_connect"))
    )
    (net (code "57") (name "unconnected-(U1-PB3-Pad26)") (class "Default")
      (node (ref "U1") (pin "26") (pinfunction "PB3_26") (pintype "unspecified+no_connect"))
    )
    (net (code "58") (name "unconnected-(U1-PB8-Pad32)") (class "Default")
      (node (ref "U1") (pin "32") (pinfunction "PB8_32") (pintype "unspecified+no_connect"))
    )
    (net (code "59") (name "unconnected-(U1-PC14-OSC_IN-Pad2)") (class "Default")
      (node (ref "U1") (pin "2") (pinfunction "PC14-OSC_IN_2") (pintype "unspecified+no_connect"))
    )
    (net (code "60") (name "unconnected-(U1-PC15-OSC_OUT-Pad3)") (class "Default")
      (node (ref "U1") (pin "3") (pinfunction "PC15-OSC_OUT_3") (pintype "unspecified+no_connect"))
    )
    (net (code "61") (name "unconnected-(U4-INT_DRDY-Pad7)") (class "Default")
      (node (ref "U4") (pin "7") (pinfunction "INT_DRDY_7") (pintype "unspecified+no_connect"))
    )
    (net (code "62") (name "unconnected-(U8-GPOUT-Pad12)") (class "Default")
      (node (ref "U8") (pin "12") (pinfunction "GPOUT_12") (pintype "input+no_connect"))
    )
    (net (code "63") (name "unconnected-(U8-NC-Pad4)") (class "Default")
      (node (ref "U8") (pin "4") (pinfunction "NC_4") (pintype "input+no_connect"))
    )
    (net (code "64") (name "unconnected-(U8-NC-Pad9)") (class "Default")
      (node (ref "U8") (pin "9") (pinfunction "NC_9") (pintype "input+no_connect"))
    )
    (net (code "65") (name "unconnected-(U8-NC-Pad11)") (class "Default")
      (node (ref "U8") (pin "11") (pinfunction "NC_11") (pintype "input+no_connect"))
    )
    (net (code "66") (name "unconnected-(U13-ADC-Pad7)") (class "Default")
      (node (ref "U13") (pin "7") (pinfunction "ADC_7") (pintype "unspecified+no_connect"))
    )
    (net (code "67") (name "unconnected-(U13-AT-Pad6)") (class "Default")
      (node (ref "U13") (pin "6") (pinfunction "AT_6") (pintype "unspecified+no_connect"))
    )
    (net (code "68") (name "unconnected-(U13-CTS#-Pad13)") (class "Default")
      (node (ref "U13") (pin "13") (pinfunction "CTS#_13") (pintype "unspecified+no_connect"))
    )
    (net (code "69") (name "unconnected-(U13-DCD#{slash}GPIO7-Pad8)") (class "Default")
      (node (ref "U13") (pin "8") (pinfunction "DCD#/GPIO7_8") (pintype "unspecified+no_connect"))
    )
    (net (code "70") (name "unconnected-(U13-DSR#{slash}GPIO6-Pad9)") (class "Default")
      (node (ref "U13") (pin "9") (pinfunction "DSR#/GPIO6_9") (pintype "unspecified+no_connect"))
    )
    (net (code "71") (name "unconnected-(U13-GPIO0-Pad28)") (class "Default")
      (node (ref "U13") (pin "28") (pinfunction "GPIO0_28") (pintype "unspecified+no_connect"))
    )
    (net (code "72") (name "unconnected-(U13-GPIO1-Pad27)") (class "Default")
      (node (ref "U13") (pin "27") (pinfunction "GPIO1_27") (pintype "unspecified+no_connect"))
    )
    (net (code "73") (name "unconnected-(U13-GPIO2-Pad26)") (class "Default")
      (node (ref "U13") (pin "26") (pinfunction "GPIO2_26") (pintype "unspecified+no_connect"))
    )
    (net (code "74") (name "unconnected-(U13-GPIO3-Pad25)") (class "Default")
      (node (ref "U13") (pin "25") (pinfunction "GPIO3_25") (pintype "unspecified+no_connect"))
    )
    (net (code "75") (name "unconnected-(U13-NC-Pad17)") (class "Default")
      (node (ref "U13") (pin "17") (pinfunction "NC_17") (pintype "unspecified+no_connect"))
    )
    (net (code "76") (name "unconnected-(U13-RELOAD{slash}LED-Pad23)") (class "Default")
      (node (ref "U13") (pin "23") (pinfunction "RELOAD/LED_23") (pintype "unspecified+no_connect"))
    )
    (net (code "77") (name "unconnected-(U13-RI#{slash}GPIO5-Pad10)") (class "Default")
      (node (ref "U13") (pin "10") (pinfunction "RI#/GPIO5_10") (pintype "unspecified+no_connect"))
    )
    (net (code "78") (name "unconnected-(U13-RST#-Pad16)") (class "Default")
      (node (ref "U13") (pin "16") (pinfunction "RST#_16") (pintype "unspecified+no_connect"))
    )
    (net (code "79") (name "unconnected-(U13-RTS#{slash}TNOW-Pad12)") (class "Default")
      (node (ref "U13") (pin "12") (pinfunction "RTS#/TNOW_12") (pintype "unspecified+no_connect"))
    )
    (net (code "80") (name "unconnected-(U13-SLEEP-Pad24)") (class "Default")
      (node (ref "U13") (pin "24") (pinfunction "SLEEP_24") (pintype "unspecified+no_connect"))
    )
    (net (code "81") (name "unconnected-(U13-X32KI-Pad2)") (class "Default")
      (node (ref "U13") (pin "2") (pinfunction "X32KI_2") (pintype "unspecified+no_connect"))
    )
    (net (code "82") (name "unconnected-(U13-X32KO-Pad1)") (class "Default")
      (node (ref "U13") (pin "1") (pinfunction "X32KO_1") (pintype "unspecified+no_connect"))
    )
    (net (code "83") (name "unconnected-(U14-Pad2)") (class "Default")
      (node (ref "U14") (pin "2") (pinfunction "2_2") (pintype "unspecified+no_connect"))
    )
  )
)
